# DRAM_and_QSPI.net
KiCad netlist of a schematic drawn in Altium Designer
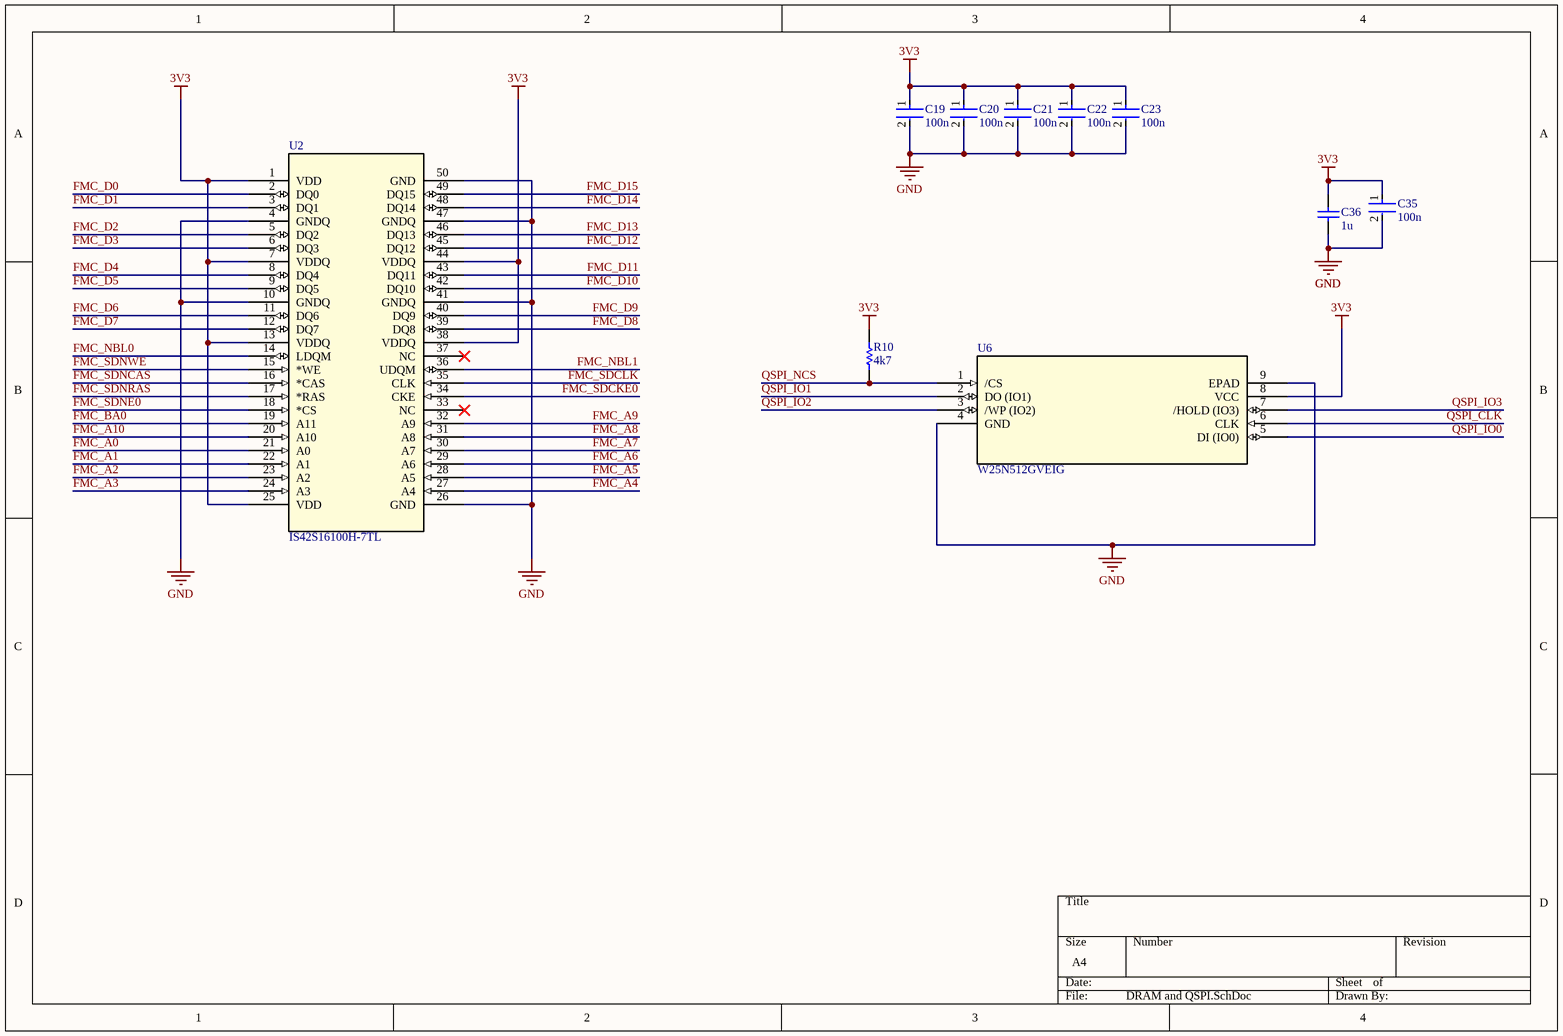
[diagram p0: DRAM and QSPI.SchDoc]

(export (version "E")
  (design (tool "Eeschema 10.0.6"))
  (components
    (comp (ref "C19")
      (value "100n")
      (footprint "FP-GRM188-0_1-e0_2_0_55-IPC_A")
      (description "Chip Multilayer Ceramic Capacitors for General Purpose, 0603, 10uF, X5R, 15%, 20%, 6.3V")
      (fields (field (name "VOLTAGE") "6.3V") (field (name "TOLERANCE") "20%"))
      (libsource (lib "Altium Content Vault") (part "02cd4be3c70576c341d710602a673aa"))
    )
    (comp (ref "C20")
      (value "100n")
      (footprint "FP-GRM188-0_1-e0_2_0_55-IPC_A")
      (description "Chip Multilayer Ceramic Capacitors for General Purpose, 0603, 10uF, X5R, 15%, 20%, 6.3V")
      (fields (field (name "VOLTAGE") "6.3V") (field (name "TOLERANCE") "20%"))
      (libsource (lib "Altium Content Vault") (part "02cd4be3c70576c341d710602a673aa"))
    )
    (comp (ref "C21")
      (value "100n")
      (footprint "FP-GRM188-0_1-e0_2_0_55-IPC_A")
      (description "Chip Multilayer Ceramic Capacitors for General Purpose, 0603, 10uF, X5R, 15%, 20%, 6.3V")
      (fields (field (name "VOLTAGE") "6.3V") (field (name "TOLERANCE") "20%"))
      (libsource (lib "Altium Content Vault") (part "02cd4be3c70576c341d710602a673aa"))
    )
    (comp (ref "C22")
      (value "100n")
      (footprint "FP-GRM188-0_1-e0_2_0_55-IPC_A")
      (description "Chip Multilayer Ceramic Capacitors for General Purpose, 0603, 10uF, X5R, 15%, 20%, 6.3V")
      (fields (field (name "VOLTAGE") "6.3V") (field (name "TOLERANCE") "20%"))
      (libsource (lib "Altium Content Vault") (part "02cd4be3c70576c341d710602a673aa"))
    )
    (comp (ref "C23")
      (value "100n")
      (footprint "FP-GRM188-0_1-e0_2_0_55-IPC_A")
      (description "Chip Multilayer Ceramic Capacitors for General Purpose, 0603, 10uF, X5R, 15%, 20%, 6.3V")
      (fields (field (name "VOLTAGE") "6.3V") (field (name "TOLERANCE") "20%"))
      (libsource (lib "Altium Content Vault") (part "02cd4be3c70576c341d710602a673aa"))
    )
    (comp (ref "C35")
      (value "100n")
      (footprint "FP-GRM188-0_1-e0_2_0_55-IPC_A")
      (description "Chip Multilayer Ceramic Capacitors for General Purpose, 0603, 10uF, X5R, 15%, 20%, 6.3V")
      (fields (field (name "VOLTAGE") "6.3V") (field (name "TOLERANCE") "20%"))
      (libsource (lib "Altium Content Vault") (part "02cd4be3c70576c341d710602a673aa"))
    )
    (comp (ref "C36")
      (value "1u")
      (footprint "CAPC2013X135X45LL10T25")
      (description "Chip Capacitor, 4.7 uF, +/- 10%, 16 V, -55 to 85 degC, 0805 (2012 Metric), RoHS, Tape and Reel")
      (fields (field (name "TOLERANCE") "10%") (field (name "PARTNUMBER") "GRM21BR61C475KA88L"))
      (libsource (lib "Altium Content Vault") (part "CAP-NP-2"))
    )
    (comp (ref "R10")
      (value "4k7")
      (footprint "RESC1608X55X30ML15T15")
      (fields (field (name "PART NUMBER") "ERJ-3EKF1003V") (field (name "MANUFACTURER") "Panasonic"))
      (libsource (lib "Altium Content Vault") (part "RES"))
    )
    (comp (ref "U2")
      (value "IS42S16100H-7TL")
      (footprint "TSOPII_50L_400MIL_ISI")
      (description "No Description Available")
      (libsource (lib "Master") (part "IS42S16100H-7TL"))
    )
    (comp (ref "U6")
      (value "W25N512GVEIG")
      (footprint "WSON8_8x6_E_WIN")
      (description "No Description Available")
      (libsource (lib "Master") (part "W25N512GVEIG"))
    )
  )
  (nets
    (net (code "1") (name "/FMC_A0") (class "Default")
      (node (ref "U2") (pin "21") (pinfunction "A0_21") (pintype "input"))
    )
    (net (code "2") (name "/FMC_A1") (class "Default")
      (node (ref "U2") (pin "22") (pinfunction "A1_22") (pintype "input"))
    )
    (net (code "3") (name "/FMC_A2") (class "Default")
      (node (ref "U2") (pin "23") (pinfunction "A2_23") (pintype "input"))
    )
    (net (code "4") (name "/FMC_A3") (class "Default")
      (node (ref "U2") (pin "24") (pinfunction "A3_24") (pintype "input"))
    )
    (net (code "5") (name "/FMC_A4") (class "Default")
      (node (ref "U2") (pin "27") (pinfunction "A4_27") (pintype "input"))
    )
    (net (code "6") (name "/FMC_A5") (class "Default")
      (node (ref "U2") (pin "28") (pinfunction "A5_28") (pintype "input"))
    )
    (net (code "7") (name "/FMC_A6") (class "Default")
      (node (ref "U2") (pin "29") (pinfunction "A6_29") (pintype "input"))
    )
    (net (code "8") (name "/FMC_A7") (class "Default")
      (node (ref "U2") (pin "30") (pinfunction "A7_30") (pintype "input"))
    )
    (net (code "9") (name "/FMC_A8") (class "Default")
      (node (ref "U2") (pin "31") (pinfunction "A8_31") (pintype "input"))
    )
    (net (code "10") (name "/FMC_A9") (class "Default")
      (node (ref "U2") (pin "32") (pinfunction "A9_32") (pintype "input"))
    )
    (net (code "11") (name "/FMC_A10") (class "Default")
      (node (ref "U2") (pin "20") (pinfunction "A10_20") (pintype "input"))
    )
    (net (code "12") (name "/FMC_BA0") (class "Default")
      (node (ref "U2") (pin "19") (pinfunction "A11_19") (pintype "input"))
    )
    (net (code "13") (name "/FMC_D0") (class "Default")
      (node (ref "U2") (pin "2") (pinfunction "DQ0_2") (pintype "bidirectional"))
    )
    (net (code "14") (name "/FMC_D1") (class "Default")
      (node (ref "U2") (pin "3") (pinfunction "DQ1_3") (pintype "bidirectional"))
    )
    (net (code "15") (name "/FMC_D2") (class "Default")
      (node (ref "U2") (pin "5") (pinfunction "DQ2_5") (pintype "bidirectional"))
    )
    (net (code "16") (name "/FMC_D3") (class "Default")
      (node (ref "U2") (pin "6") (pinfunction "DQ3_6") (pintype "bidirectional"))
    )
    (net (code "17") (name "/FMC_D4") (class "Default")
      (node (ref "U2") (pin "8") (pinfunction "DQ4_8") (pintype "bidirectional"))
    )
    (net (code "18") (name "/FMC_D5") (class "Default")
      (node (ref "U2") (pin "9") (pinfunction "DQ5_9") (pintype "bidirectional"))
    )
    (net (code "19") (name "/FMC_D6") (class "Default")
      (node (ref "U2") (pin "11") (pinfunction "DQ6_11") (pintype "bidirectional"))
    )
    (net (code "20") (name "/FMC_D7") (class "Default")
      (node (ref "U2") (pin "12") (pinfunction "DQ7_12") (pintype "bidirectional"))
    )
    (net (code "21") (name "/FMC_D8") (class "Default")
      (node (ref "U2") (pin "39") (pinfunction "DQ8_39") (pintype "bidirectional"))
    )
    (net (code "22") (name "/FMC_D9") (class "Default")
      (node (ref "U2") (pin "40") (pinfunction "DQ9_40") (pintype "bidirectional"))
    )
    (net (code "23") (name "/FMC_D10") (class "Default")
      (node (ref "U2") (pin "42") (pinfunction "DQ10_42") (pintype "bidirectional"))
    )
    (net (code "24") (name "/FMC_D11") (class "Default")
      (node (ref "U2") (pin "43") (pinfunction "DQ11_43") (pintype "bidirectional"))
    )
    (net (code "25") (name "/FMC_D12") (class "Default")
      (node (ref "U2") (pin "45") (pinfunction "DQ12_45") (pintype "bidirectional"))
    )
    (net (code "26") (name "/FMC_D13") (class "Default")
      (node (ref "U2") (pin "46") (pinfunction "DQ13_46") (pintype "bidirectional"))
    )
    (net (code "27") (name "/FMC_D14") (class "Default")
      (node (ref "U2") (pin "48") (pinfunction "DQ14_48") (pintype "bidirectional"))
    )
    (net (code "28") (name "/FMC_D15") (class "Default")
      (node (ref "U2") (pin "49") (pinfunction "DQ15_49") (pintype "bidirectional"))
    )
    (net (code "29") (name "/FMC_NBL0") (class "Default")
      (node (ref "U2") (pin "14") (pinfunction "LDQM_14") (pintype "bidirectional"))
    )
    (net (code "30") (name "/FMC_NBL1") (class "Default")
      (node (ref "U2") (pin "36") (pinfunction "UDQM_36") (pintype "bidirectional"))
    )
    (net (code "31") (name "/FMC_SDCKE0") (class "Default")
      (node (ref "U2") (pin "34") (pinfunction "CKE_34") (pintype "input"))
    )
    (net (code "32") (name "/FMC_SDCLK") (class "Default")
      (node (ref "U2") (pin "35") (pinfunction "CLK_35") (pintype "input"))
    )
    (net (code "33") (name "/FMC_SDNCAS") (class "Default")
      (node (ref "U2") (pin "16") (pinfunction "*CAS_16") (pintype "input"))
    )
    (net (code "34") (name "/FMC_SDNE0") (class "Default")
      (node (ref "U2") (pin "18") (pinfunction "*CS_18") (pintype "input"))
    )
    (net (code "35") (name "/FMC_SDNRAS") (class "Default")
      (node (ref "U2") (pin "17") (pinfunction "*RAS_17") (pintype "input"))
    )
    (net (code "36") (name "/FMC_SDNWE") (class "Default")
      (node (ref "U2") (pin "15") (pinfunction "*WE_15") (pintype "input"))
    )
    (net (code "37") (name "/QSPI_CLK") (class "Default")
      (node (ref "U6") (pin "6") (pinfunction "CLK_6") (pintype "input"))
    )
    (net (code "38") (name "/QSPI_IO0") (class "Default")
      (node (ref "U6") (pin "5") (pinfunction "DI_(IO0)_5") (pintype "bidirectional"))
    )
    (net (code "39") (name "/QSPI_IO1") (class "Default")
      (node (ref "U6") (pin "2") (pinfunction "DO_(IO1)_2") (pintype "bidirectional"))
    )
    (net (code "40") (name "/QSPI_IO2") (class "Default")
      (node (ref "U6") (pin "3") (pinfunction "/WP_(IO2)_3") (pintype "bidirectional"))
    )
    (net (code "41") (name "/QSPI_IO3") (class "Default")
      (node (ref "U6") (pin "7") (pinfunction "/HOLD_(IO3)_7") (pintype "bidirectional"))
    )
    (net (code "42") (name "/QSPI_NCS") (class "Default")
      (node (ref "R10") (pin "1") (pinfunction "1_1") (pintype "passive"))
      (node (ref "U6") (pin "1") (pinfunction "/CS_1") (pintype "input"))
    )
    (net (code "43") (name "3V3") (class "Default")
      (node (ref "C19") (pin "1") (pinfunction "1_1") (pintype "passive"))
      (node (ref "C20") (pin "1") (pinfunction "1_1") (pintype "passive"))
      (node (ref "C21") (pin "1") (pinfunction "1_1") (pintype "passive"))
      (node (ref "C22") (pin "1") (pinfunction "1_1") (pintype "passive"))
      (node (ref "C23") (pin "1") (pinfunction "1_1") (pintype "passive"))
      (node (ref "C35") (pin "1") (pinfunction "1_1") (pintype "passive"))
      (node (ref "C36") (pin "2") (pinfunction "2_2") (pintype "passive"))
      (node (ref "R10") (pin "2") (pinfunction "2_2") (pintype "passive"))
      (node (ref "U2") (pin "1") (pinfunction "VDD_1") (pintype "power_in"))
      (node (ref "U2") (pin "13") (pinfunction "VDDQ_13") (pintype "power_in"))
      (node (ref "U2") (pin "25") (pinfunction "VDD_25") (pintype "power_in"))
      (node (ref "U2") (pin "38") (pinfunction "VDDQ_38") (pintype "power_in"))
      (node (ref "U2") (pin "44") (pinfunction "VDDQ_44") (pintype "power_in"))
      (node (ref "U2") (pin "7") (pinfunction "VDDQ_7") (pintype "power_in"))
      (node (ref "U6") (pin "8") (pinfunction "VCC_8") (pintype "power_in"))
    )
    (net (code "44") (name "GND") (class "Default")
      (node (ref "C19") (pin "2") (pinfunction "2_2") (pintype "passive"))
      (node (ref "C20") (pin "2") (pinfunction "2_2") (pintype "passive"))
      (node (ref "C21") (pin "2") (pinfunction "2_2") (pintype "passive"))
      (node (ref "C22") (pin "2") (pinfunction "2_2") (pintype "passive"))
      (node (ref "C23") (pin "2") (pinfunction "2_2") (pintype "passive"))
      (node (ref "C35") (pin "2") (pinfunction "2_2") (pintype "passive"))
      (node (ref "C36") (pin "1") (pinfunction "1_1") (pintype "passive"))
      (node (ref "U2") (pin "10") (pinfunction "GNDQ_10") (pintype "power_in"))
      (node (ref "U2") (pin "26") (pinfunction "GND_26") (pintype "power_in"))
      (node (ref "U2") (pin "4") (pinfunction "GNDQ_4") (pintype "power_in"))
      (node (ref "U2") (pin "41") (pinfunction "GNDQ_41") (pintype "power_in"))
      (node (ref "U2") (pin "47") (pinfunction "GNDQ_47") (pintype "power_in"))
      (node (ref "U2") (pin "50") (pinfunction "GND_50") (pintype "power_in"))
      (node (ref "U6") (pin "4") (pinfunction "GND_4") (pintype "power_in"))
      (node (ref "U6") (pin "9") (pinfunction "EPAD_9") (pintype "passive"))
    )
    (net (code "45") (name "unconnected-(U2-NC-Pad33)") (class "Default")
      (node (ref "U2") (pin "33") (pinfunction "NC_33") (pintype "passive+no_connect"))
    )
    (net (code "46") (name "unconnected-(U2-NC-Pad37)") (class "Default")
      (node (ref "U2") (pin "37") (pinfunction "NC_37") (pintype "passive+no_connect"))
    )
  )
)
